# Switch_Mini.net
KiCad netlist of a schematic drawn in EAGLE
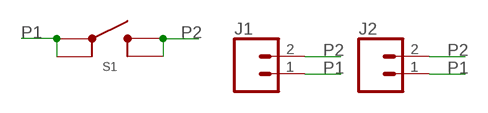
[diagram p0: schematic, sheet 1]

(export (version "E")
  (design (tool "Eeschema 10.0.6"))
  (components
    (comp (ref "J1")
      (value "CONN_02")
      (footprint "eagle-import:1X02")
      (libsource (lib "eagle-import") (part "CONN_02"))
    )
    (comp (ref "J2")
      (value "CONN_02")
      (footprint "eagle-import:1X02")
      (libsource (lib "eagle-import") (part "CONN_02"))
    )
    (comp (ref "S1")
      (value "BUTTON4.2X3.2")
      (footprint "eagle-import:SWITCH_4.2X3.2")
      (fields (field (name "MF") "C&K") (field (name "MPN") "PTS810 SJG 250 SMTR LFS"))
      (libsource (lib "eagle-import") (part "BUTTON4.2X3.2"))
    )
  )
  (nets
    (net (code "1") (name "/P1") (class "Default")
      (node (ref "J1") (pin "1") (pinfunction "1_1") (pintype "passive"))
      (node (ref "J2") (pin "1") (pinfunction "1_1") (pintype "passive"))
      (node (ref "S1") (pin "1") (pinfunction "1_1") (pintype "bidirectional"))
      (node (ref "S1") (pin "2") (pinfunction "2_2") (pintype "bidirectional"))
    )
    (net (code "2") (name "/P2") (class "Default")
      (node (ref "J1") (pin "2") (pinfunction "2_2") (pintype "passive"))
      (node (ref "J2") (pin "2") (pinfunction "2_2") (pintype "passive"))
      (node (ref "S1") (pin "3") (pinfunction "4_3") (pintype "bidirectional"))
      (node (ref "S1") (pin "4") (pinfunction "3_4") (pintype "bidirectional"))
    )
  )
)
